# Sheet1.net
KiCad netlist of a schematic drawn in Altium Designer
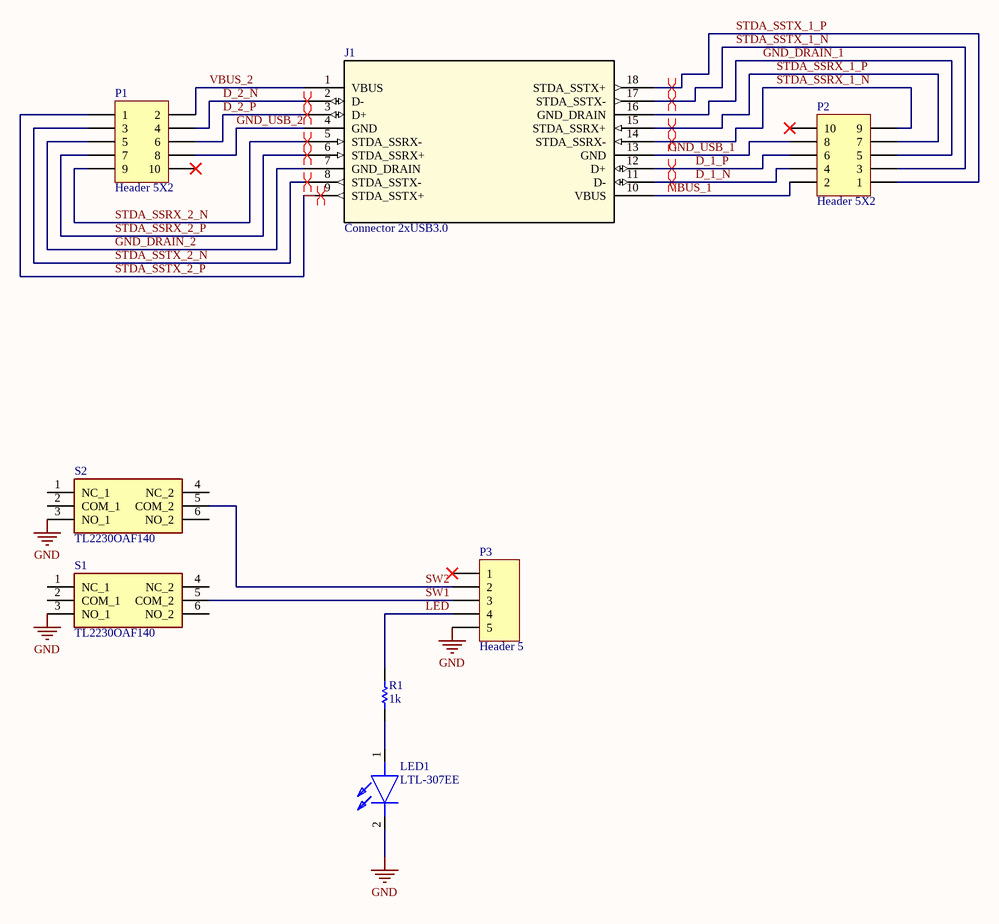
[diagram p0: Sheet1.SchDoc]

(export (version "E")
  (design (tool "Eeschema 10.0.6"))
  (components
    (comp (ref "J1")
      (value "Connector 2xUSB3.0")
      (footprint "48409-0003")
      (description "Conector 2xUSB3.0 Molex")
      (fields
        (field (name "MANUFACTURER_PART_NUMBER") "484090003")
        (field (name "COPYRIGHT") "Copyright (C) 2021 Ultra Librarian. All rights reserved.")
      )
      (libsource (lib "GeekLibPCB") (part "48409-0003"))
    )
    (comp (ref "LED1")
      (value "LTL-307EE")
      (footprint "LTL307YE")
      (description "LED Red")
      (libsource (lib "GeekLibPCB") (part "LTL-307EE"))
    )
    (comp (ref "P1")
      (value "Header 5X2")
      (footprint "HDR2X5")
      (description "Header, 5-Pin, Dual row")
      (fields (field (name "PUBLISHER") "Altium Limited"))
      (libsource (lib "") (part "Header 5X2_1"))
    )
    (comp (ref "P2")
      (value "Header 5X2")
      (footprint "HDR2X5")
      (description "Header, 5-Pin, Dual row")
      (fields (field (name "PUBLISHER") "Altium Limited"))
      (libsource (lib "Miscellaneous Connectors") (part "Header 5X2"))
    )
    (comp (ref "P3")
      (value "Header 5")
      (footprint "HDR1X5")
      (description "Header, 5-Pin")
      (fields (field (name "PUBLISHER") "Altium Limited"))
      (libsource (lib "Miscellaneous Connectors") (part "Header 5"))
    )
    (comp (ref "R1")
      (value "1k")
      (footprint "res-smd-0603")
      (description "Resistor")
      (fields (field (name "PUBLISHER") "Altium Limited"))
      (libsource (lib "GeekLibPCB") (part "Res1"))
    )
    (comp (ref "S1")
      (value "TL2230OAF140")
      (footprint "TL2230OAF140")
      (description "Switch Momentary")
      (fields (field (name "MOUSER2 PART NUMBER") "612-TL2230-OA"))
      (libsource (lib "GeekLibPCB") (part "TL2230OAF140"))
    )
    (comp (ref "S2")
      (value "TL2230OAF140")
      (footprint "TL2230OAF140")
      (description "Switch Momentary")
      (fields (field (name "MOUSER2 PART NUMBER") "612-TL2230-OA"))
      (libsource (lib "GeekLibPCB") (part "TL2230OAF140"))
    )
  )
  (nets
    (net (code "1") (name "/D_1_N") (class "Default")
      (node (ref "J1") (pin "11") (pinfunction "D-_11") (pintype "bidirectional"))
      (node (ref "P2") (pin "4") (pinfunction "4_4") (pintype "passive"))
    )
    (net (code "2") (name "/D_1_P") (class "Default")
      (node (ref "J1") (pin "12") (pinfunction "D+_12") (pintype "bidirectional"))
      (node (ref "P2") (pin "6") (pinfunction "6_6") (pintype "passive"))
    )
    (net (code "3") (name "/D_2_N") (class "Default")
      (node (ref "J1") (pin "2") (pinfunction "D-_2") (pintype "bidirectional"))
      (node (ref "P1") (pin "4") (pinfunction "4_4") (pintype "passive"))
    )
    (net (code "4") (name "/D_2_P") (class "Default")
      (node (ref "J1") (pin "3") (pinfunction "D+_3") (pintype "bidirectional"))
      (node (ref "P1") (pin "6") (pinfunction "6_6") (pintype "passive"))
    )
    (net (code "5") (name "/GND_DRAIN_1") (class "Default")
      (node (ref "J1") (pin "16") (pinfunction "GND_DRAIN_16") (pintype "passive"))
      (node (ref "P2") (pin "5") (pinfunction "5_5") (pintype "passive"))
    )
    (net (code "6") (name "/GND_DRAIN_2") (class "Default")
      (node (ref "J1") (pin "7") (pinfunction "GND_DRAIN_7") (pintype "passive"))
      (node (ref "P1") (pin "5") (pinfunction "5_5") (pintype "passive"))
    )
    (net (code "7") (name "/GND_USB_1") (class "Default")
      (node (ref "J1") (pin "13") (pinfunction "GND_13") (pintype "passive"))
      (node (ref "P2") (pin "8") (pinfunction "8_8") (pintype "passive"))
    )
    (net (code "8") (name "/GND_USB_2") (class "Default")
      (node (ref "J1") (pin "4") (pinfunction "GND_4") (pintype "passive"))
      (node (ref "P1") (pin "8") (pinfunction "8_8") (pintype "passive"))
    )
    (net (code "9") (name "/LED") (class "Default")
      (node (ref "P3") (pin "4") (pinfunction "4_4") (pintype "passive"))
      (node (ref "R1") (pin "2") (pinfunction "2_2") (pintype "passive"))
    )
    (net (code "10") (name "/STDA_SSRX_1_N") (class "Default")
      (node (ref "J1") (pin "14") (pinfunction "STDA_SSRX-_14") (pintype "input"))
      (node (ref "P2") (pin "9") (pinfunction "9_9") (pintype "passive"))
    )
    (net (code "11") (name "/STDA_SSRX_1_P") (class "Default")
      (node (ref "J1") (pin "15") (pinfunction "STDA_SSRX+_15") (pintype "input"))
      (node (ref "P2") (pin "7") (pinfunction "7_7") (pintype "passive"))
    )
    (net (code "12") (name "/STDA_SSRX_2_N") (class "Default")
      (node (ref "J1") (pin "5") (pinfunction "STDA_SSRX-_5") (pintype "input"))
      (node (ref "P1") (pin "9") (pinfunction "9_9") (pintype "passive"))
    )
    (net (code "13") (name "/STDA_SSRX_2_P") (class "Default")
      (node (ref "J1") (pin "6") (pinfunction "STDA_SSRX+_6") (pintype "input"))
      (node (ref "P1") (pin "7") (pinfunction "7_7") (pintype "passive"))
    )
    (net (code "14") (name "/STDA_SSTX_1_N") (class "Default")
      (node (ref "J1") (pin "17") (pinfunction "STDA_SSTX-_17") (pintype "output"))
      (node (ref "P2") (pin "3") (pinfunction "3_3") (pintype "passive"))
    )
    (net (code "15") (name "/STDA_SSTX_1_P") (class "Default")
      (node (ref "J1") (pin "18") (pinfunction "STDA_SSTX+_18") (pintype "output"))
      (node (ref "P2") (pin "1") (pinfunction "1_1") (pintype "passive"))
    )
    (net (code "16") (name "/STDA_SSTX_2_N") (class "Default")
      (node (ref "J1") (pin "8") (pinfunction "STDA_SSTX-_8") (pintype "output"))
      (node (ref "P1") (pin "3") (pinfunction "3_3") (pintype "passive"))
    )
    (net (code "17") (name "/STDA_SSTX_2_P") (class "Default")
      (node (ref "J1") (pin "9") (pinfunction "STDA_SSTX+_9") (pintype "output"))
      (node (ref "P1") (pin "1") (pinfunction "1_1") (pintype "passive"))
    )
    (net (code "18") (name "/SW1") (class "Default")
      (node (ref "P3") (pin "3") (pinfunction "3_3") (pintype "passive"))
      (node (ref "S1") (pin "5") (pinfunction "COM_2_5") (pintype "passive"))
    )
    (net (code "19") (name "/SW2") (class "Default")
      (node (ref "P3") (pin "2") (pinfunction "2_2") (pintype "passive"))
      (node (ref "S2") (pin "5") (pinfunction "COM_2_5") (pintype "passive"))
    )
    (net (code "20") (name "/VBUS_1") (class "Default")
      (node (ref "J1") (pin "10") (pinfunction "VBUS_10") (pintype "power_in"))
      (node (ref "P2") (pin "2") (pinfunction "2_2") (pintype "passive"))
    )
    (net (code "21") (name "/VBUS_2") (class "Default")
      (node (ref "J1") (pin "1") (pinfunction "VBUS_1") (pintype "power_in"))
      (node (ref "P1") (pin "2") (pinfunction "2_2") (pintype "passive"))
    )
    (net (code "22") (name "GND") (class "Default")
      (node (ref "LED1") (pin "2") (pinfunction "K_2") (pintype "passive"))
      (node (ref "P3") (pin "5") (pinfunction "5_5") (pintype "passive"))
      (node (ref "S1") (pin "3") (pinfunction "NO_1_3") (pintype "passive"))
      (node (ref "S2") (pin "3") (pinfunction "NO_1_3") (pintype "passive"))
    )
    (net (code "23") (name "Net-(LED1-A)") (class "Default")
      (node (ref "LED1") (pin "1") (pinfunction "A_1") (pintype "passive"))
      (node (ref "R1") (pin "1") (pinfunction "1_1") (pintype "passive"))
    )
    (net (code "24") (name "unconnected-(P1-Pad10)") (class "Default")
      (node (ref "P1") (pin "10") (pinfunction "10_10") (pintype "passive+no_connect"))
    )
    (net (code "25") (name "unconnected-(P2-Pad10)") (class "Default")
      (node (ref "P2") (pin "10") (pinfunction "10_10") (pintype "passive+no_connect"))
    )
    (net (code "26") (name "unconnected-(P3-Pad1)") (class "Default")
      (node (ref "P3") (pin "1") (pinfunction "1_1") (pintype "passive+no_connect"))
    )
    (net (code "27") (name "unconnected-(S1-COM_1-Pad2)") (class "Default")
      (node (ref "S1") (pin "2") (pinfunction "COM_1_2") (pintype "passive"))
    )
    (net (code "28") (name "unconnected-(S1-NC_1-Pad1)") (class "Default")
      (node (ref "S1") (pin "1") (pinfunction "NC_1_1") (pintype "passive"))
    )
    (net (code "29") (name "unconnected-(S1-NC_2-Pad4)") (class "Default")
      (node (ref "S1") (pin "4") (pinfunction "NC_2_4") (pintype "passive"))
    )
    (net (code "30") (name "unconnected-(S1-NO_2-Pad6)") (class "Default")
      (node (ref "S1") (pin "6") (pinfunction "NO_2_6") (pintype "passive"))
    )
    (net (code "31") (name "unconnected-(S2-COM_1-Pad2)") (class "Default")
      (node (ref "S2") (pin "2") (pinfunction "COM_1_2") (pintype "passive"))
    )
    (net (code "32") (name "unconnected-(S2-NC_1-Pad1)") (class "Default")
      (node (ref "S2") (pin "1") (pinfunction "NC_1_1") (pintype "passive"))
    )
    (net (code "33") (name "unconnected-(S2-NC_2-Pad4)") (class "Default")
      (node (ref "S2") (pin "4") (pinfunction "NC_2_4") (pintype "passive"))
    )
    (net (code "34") (name "unconnected-(S2-NO_2-Pad6)") (class "Default")
      (node (ref "S2") (pin "6") (pinfunction "NO_2_6") (pintype "passive"))
    )
  )
)
